# design.net
KiCad netlist of a schematic drawn in Altium Designer
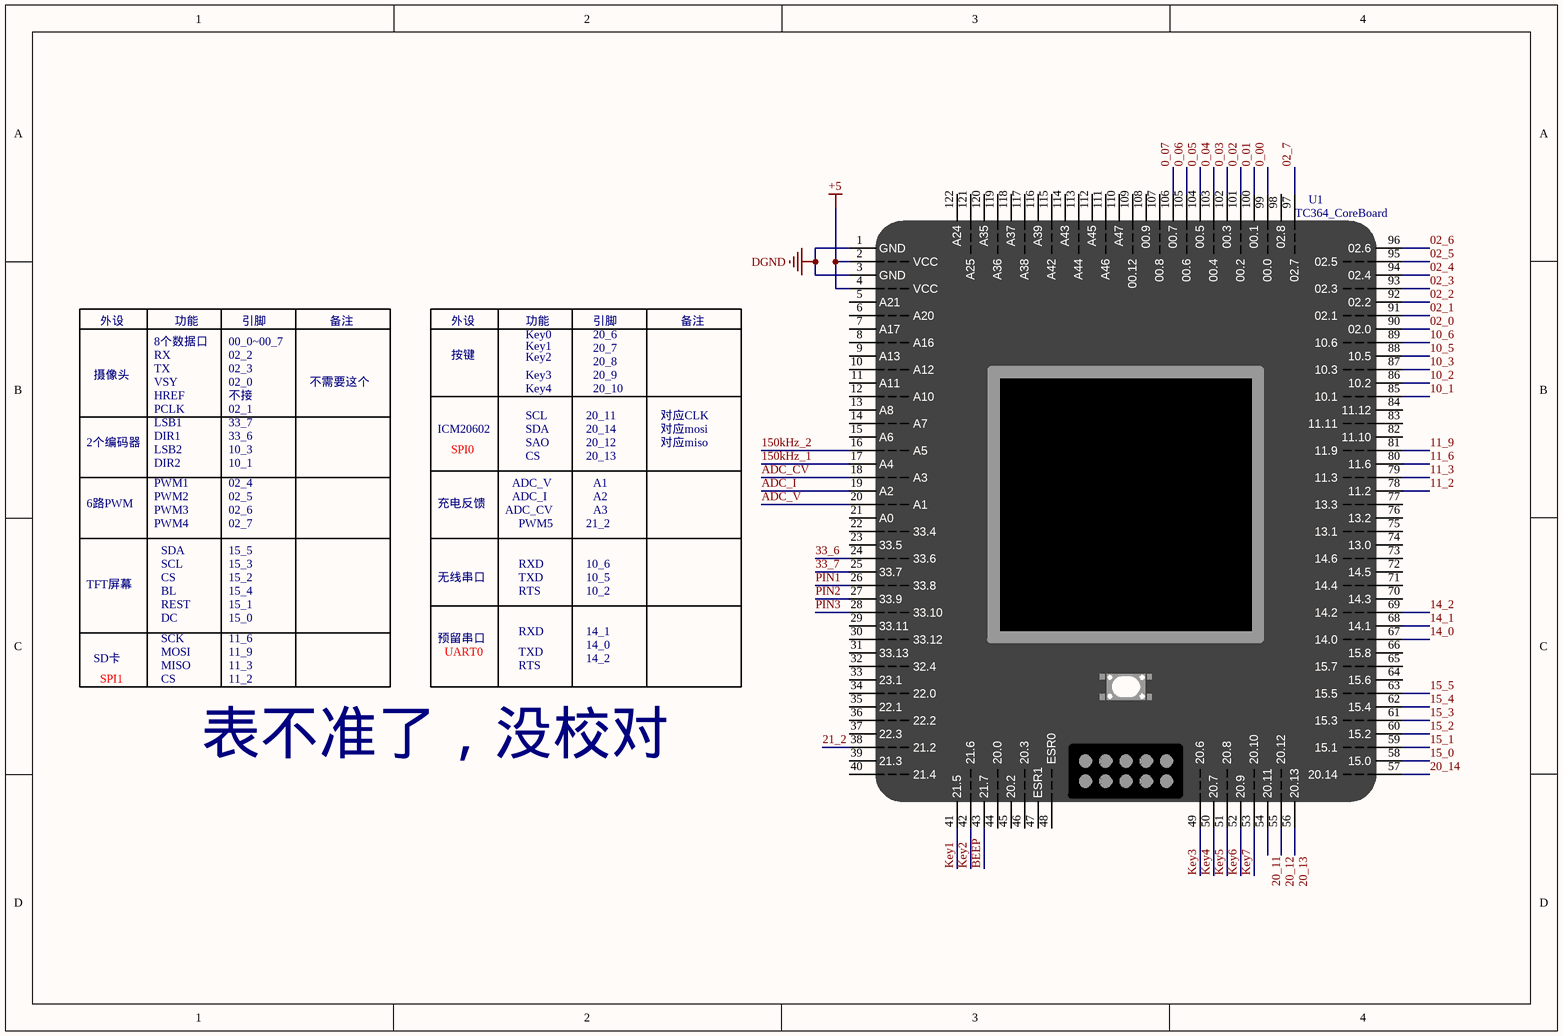
[diagram p0: 主控.SchDoc]

(export (version "E")
  (design (tool "Eeschema 10.0.6"))
  (components
    (comp (ref "U1")
      (value "TC364_CoreBoard")
      (footprint "TC364_CoreBoard")
      (description "逐飞科技TC364核心板")
      (libsource (lib "TC364") (part "TC364_CoreBoard"))
    )
  )
  (nets
    (net (code "1") (name "+5") (class "Default")
      (node (ref "U1") (pin "2") (pinfunction "VCC_2") (pintype "passive"))
      (node (ref "U1") (pin "4") (pinfunction "VCC_4") (pintype "passive"))
    )
    (net (code "2") (name "/0_00") (class "Default")
      (node (ref "U1") (pin "99") (pinfunction "00.0_99") (pintype "passive"))
    )
    (net (code "3") (name "/0_01") (class "Default")
      (node (ref "U1") (pin "100") (pinfunction "00.1_100") (pintype "passive"))
    )
    (net (code "4") (name "/0_02") (class "Default")
      (node (ref "U1") (pin "101") (pinfunction "00.2_101") (pintype "passive"))
    )
    (net (code "5") (name "/0_03") (class "Default")
      (node (ref "U1") (pin "102") (pinfunction "00.3_102") (pintype "passive"))
    )
    (net (code "6") (name "/0_04") (class "Default")
      (node (ref "U1") (pin "103") (pinfunction "00.4_103") (pintype "passive"))
    )
    (net (code "7") (name "/0_05") (class "Default")
      (node (ref "U1") (pin "104") (pinfunction "00.5_104") (pintype "passive"))
    )
    (net (code "8") (name "/0_06") (class "Default")
      (node (ref "U1") (pin "105") (pinfunction "00.6_105") (pintype "passive"))
    )
    (net (code "9") (name "/0_07") (class "Default")
      (node (ref "U1") (pin "106") (pinfunction "00.7_106") (pintype "passive"))
    )
    (net (code "10") (name "/02_0") (class "Default")
      (node (ref "U1") (pin "90") (pinfunction "02.0_90") (pintype "passive"))
    )
    (net (code "11") (name "/02_1") (class "Default")
      (node (ref "U1") (pin "91") (pinfunction "02.1_91") (pintype "passive"))
    )
    (net (code "12") (name "/02_2") (class "Default")
      (node (ref "U1") (pin "92") (pinfunction "02.2_92") (pintype "passive"))
    )
    (net (code "13") (name "/02_3") (class "Default")
      (node (ref "U1") (pin "93") (pinfunction "02.3_93") (pintype "passive"))
    )
    (net (code "14") (name "/02_4") (class "Default")
      (node (ref "U1") (pin "94") (pinfunction "02.4_94") (pintype "passive"))
    )
    (net (code "15") (name "/02_5") (class "Default")
      (node (ref "U1") (pin "95") (pinfunction "02.5_95") (pintype "passive"))
    )
    (net (code "16") (name "/02_6") (class "Default")
      (node (ref "U1") (pin "96") (pinfunction "02.6_96") (pintype "passive"))
    )
    (net (code "17") (name "/02_7") (class "Default")
      (node (ref "U1") (pin "97") (pinfunction "02.7_97") (pintype "passive"))
    )
    (net (code "18") (name "/10_1") (class "Default")
      (node (ref "U1") (pin "85") (pinfunction "10.1_85") (pintype "passive"))
    )
    (net (code "19") (name "/10_2") (class "Default")
      (node (ref "U1") (pin "86") (pinfunction "10.2_86") (pintype "passive"))
    )
    (net (code "20") (name "/10_3") (class "Default")
      (node (ref "U1") (pin "87") (pinfunction "10.3_87") (pintype "passive"))
    )
    (net (code "21") (name "/10_5") (class "Default")
      (node (ref "U1") (pin "88") (pinfunction "10.5_88") (pintype "passive"))
    )
    (net (code "22") (name "/10_6") (class "Default")
      (node (ref "U1") (pin "89") (pinfunction "10.6_89") (pintype "passive"))
    )
    (net (code "23") (name "/11_2") (class "Default")
      (node (ref "U1") (pin "78") (pinfunction "11.2_78") (pintype "passive"))
    )
    (net (code "24") (name "/11_3") (class "Default")
      (node (ref "U1") (pin "79") (pinfunction "11.3_79") (pintype "passive"))
    )
    (net (code "25") (name "/11_6") (class "Default")
      (node (ref "U1") (pin "80") (pinfunction "11.6_80") (pintype "passive"))
    )
    (net (code "26") (name "/11_9") (class "Default")
      (node (ref "U1") (pin "81") (pinfunction "11.9_81") (pintype "passive"))
    )
    (net (code "27") (name "/14_0") (class "Default")
      (node (ref "U1") (pin "67") (pinfunction "14.0_67") (pintype "passive"))
    )
    (net (code "28") (name "/14_1") (class "Default")
      (node (ref "U1") (pin "68") (pinfunction "14.1_68") (pintype "passive"))
    )
    (net (code "29") (name "/14_2") (class "Default")
      (node (ref "U1") (pin "69") (pinfunction "14.2_69") (pintype "passive"))
    )
    (net (code "30") (name "/15_0") (class "Default")
      (node (ref "U1") (pin "58") (pinfunction "15.0_58") (pintype "passive"))
    )
    (net (code "31") (name "/15_1") (class "Default")
      (node (ref "U1") (pin "59") (pinfunction "15.1_59") (pintype "passive"))
    )
    (net (code "32") (name "/15_2") (class "Default")
      (node (ref "U1") (pin "60") (pinfunction "15.2_60") (pintype "passive"))
    )
    (net (code "33") (name "/15_3") (class "Default")
      (node (ref "U1") (pin "61") (pinfunction "15.3_61") (pintype "passive"))
    )
    (net (code "34") (name "/15_4") (class "Default")
      (node (ref "U1") (pin "62") (pinfunction "15.4_62") (pintype "passive"))
    )
    (net (code "35") (name "/15_5") (class "Default")
      (node (ref "U1") (pin "63") (pinfunction "15.5_63") (pintype "passive"))
    )
    (net (code "36") (name "/20_11") (class "Default")
      (node (ref "U1") (pin "54") (pinfunction "20.11_54") (pintype "passive"))
    )
    (net (code "37") (name "/20_12") (class "Default")
      (node (ref "U1") (pin "55") (pinfunction "20.12_55") (pintype "passive"))
    )
    (net (code "38") (name "/20_13") (class "Default")
      (node (ref "U1") (pin "56") (pinfunction "20.13_56") (pintype "passive"))
    )
    (net (code "39") (name "/20_14") (class "Default")
      (node (ref "U1") (pin "57") (pinfunction "20.14_57") (pintype "passive"))
    )
    (net (code "40") (name "/21_2") (class "Default")
      (node (ref "U1") (pin "38") (pinfunction "21.2_38") (pintype "passive"))
    )
    (net (code "41") (name "/33_6") (class "Default")
      (node (ref "U1") (pin "24") (pinfunction "33.6_24") (pintype "passive"))
    )
    (net (code "42") (name "/33_7") (class "Default")
      (node (ref "U1") (pin "25") (pinfunction "33.7_25") (pintype "passive"))
    )
    (net (code "43") (name "/150kHz_1") (class "Default")
      (node (ref "U1") (pin "17") (pinfunction "A4_17") (pintype "passive"))
    )
    (net (code "44") (name "/150kHz_2") (class "Default")
      (node (ref "U1") (pin "16") (pinfunction "A5_16") (pintype "passive"))
    )
    (net (code "46") (name "/ADC_CV") (class "Default")
      (node (ref "U1") (pin "18") (pinfunction "A3_18") (pintype "passive"))
    )
    (net (code "47") (name "/ADC_I") (class "Default")
      (node (ref "U1") (pin "19") (pinfunction "A2_19") (pintype "passive"))
    )
    (net (code "48") (name "/ADC_V") (class "Default")
      (node (ref "U1") (pin "20") (pinfunction "A1_20") (pintype "passive"))
    )
    (net (code "49") (name "/BEEP") (class "Default")
      (node (ref "U1") (pin "43") (pinfunction "21.7_43") (pintype "passive"))
    )
    (net (code "50") (name "/Key1") (class "Default")
      (node (ref "U1") (pin "41") (pinfunction "21.5_41") (pintype "passive"))
    )
    (net (code "51") (name "/Key2") (class "Default")
      (node (ref "U1") (pin "42") (pinfunction "21.6_42") (pintype "passive"))
    )
    (net (code "52") (name "/Key3") (class "Default")
      (node (ref "U1") (pin "49") (pinfunction "20.6_49") (pintype "passive"))
    )
    (net (code "53") (name "/Key4") (class "Default")
      (node (ref "U1") (pin "50") (pinfunction "20.7_50") (pintype "passive"))
    )
    (net (code "54") (name "/Key5") (class "Default")
      (node (ref "U1") (pin "51") (pinfunction "20.8_51") (pintype "passive"))
    )
    (net (code "55") (name "/Key6") (class "Default")
      (node (ref "U1") (pin "52") (pinfunction "20.9_52") (pintype "passive"))
    )
    (net (code "56") (name "/Key7") (class "Default")
      (node (ref "U1") (pin "53") (pinfunction "20.10_53") (pintype "passive"))
    )
    (net (code "57") (name "/PIN1") (class "Default")
      (node (ref "U1") (pin "26") (pinfunction "33.8_26") (pintype "passive"))
    )
    (net (code "58") (name "/PIN2") (class "Default")
      (node (ref "U1") (pin "27") (pinfunction "33.9_27") (pintype "passive"))
    )
    (net (code "59") (name "/PIN3") (class "Default")
      (node (ref "U1") (pin "28") (pinfunction "33.10_28") (pintype "passive"))
    )
    (net (code "60") (name "DGND") (class "Default")
      (node (ref "U1") (pin "1") (pinfunction "GND_1") (pintype "passive"))
      (node (ref "U1") (pin "3") (pinfunction "GND_3") (pintype "passive"))
    )
    (net (code "61") (name "unconnected-(U1-00.8-Pad107)") (class "Default")
      (node (ref "U1") (pin "107") (pinfunction "00.8_107") (pintype "passive"))
    )
    (net (code "62") (name "unconnected-(U1-00.9-Pad108)") (class "Default")
      (node (ref "U1") (pin "108") (pinfunction "00.9_108") (pintype "passive"))
    )
    (net (code "63") (name "unconnected-(U1-00.12-Pad109)") (class "Default")
      (node (ref "U1") (pin "109") (pinfunction "00.12_109") (pintype "passive"))
    )
    (net (code "64") (name "unconnected-(U1-02.8-Pad98)") (class "Default")
      (node (ref "U1") (pin "98") (pinfunction "02.8_98") (pintype "passive"))
    )
    (net (code "65") (name "unconnected-(U1-11.10-Pad82)") (class "Default")
      (node (ref "U1") (pin "82") (pinfunction "11.10_82") (pintype "passive"))
    )
    (net (code "66") (name "unconnected-(U1-11.11-Pad83)") (class "Default")
      (node (ref "U1") (pin "83") (pinfunction "11.11_83") (pintype "passive"))
    )
    (net (code "67") (name "unconnected-(U1-11.12-Pad84)") (class "Default")
      (node (ref "U1") (pin "84") (pinfunction "11.12_84") (pintype "passive"))
    )
    (net (code "68") (name "unconnected-(U1-13.0-Pad74)") (class "Default")
      (node (ref "U1") (pin "74") (pinfunction "13.0_74") (pintype "passive"))
    )
    (net (code "69") (name "unconnected-(U1-13.1-Pad75)") (class "Default")
      (node (ref "U1") (pin "75") (pinfunction "13.1_75") (pintype "passive"))
    )
    (net (code "70") (name "unconnected-(U1-13.2-Pad76)") (class "Default")
      (node (ref "U1") (pin "76") (pinfunction "13.2_76") (pintype "passive"))
    )
    (net (code "71") (name "unconnected-(U1-13.3-Pad77)") (class "Default")
      (node (ref "U1") (pin "77") (pinfunction "13.3_77") (pintype "passive"))
    )
    (net (code "72") (name "unconnected-(U1-14.3-Pad70)") (class "Default")
      (node (ref "U1") (pin "70") (pinfunction "14.3_70") (pintype "passive"))
    )
    (net (code "73") (name "unconnected-(U1-14.4-Pad71)") (class "Default")
      (node (ref "U1") (pin "71") (pinfunction "14.4_71") (pintype "passive"))
    )
    (net (code "74") (name "unconnected-(U1-14.5-Pad72)") (class "Default")
      (node (ref "U1") (pin "72") (pinfunction "14.5_72") (pintype "passive"))
    )
    (net (code "75") (name "unconnected-(U1-14.6-Pad73)") (class "Default")
      (node (ref "U1") (pin "73") (pinfunction "14.6_73") (pintype "passive"))
    )
    (net (code "76") (name "unconnected-(U1-15.6-Pad64)") (class "Default")
      (node (ref "U1") (pin "64") (pinfunction "15.6_64") (pintype "passive"))
    )
    (net (code "77") (name "unconnected-(U1-15.7-Pad65)") (class "Default")
      (node (ref "U1") (pin "65") (pinfunction "15.7_65") (pintype "passive"))
    )
    (net (code "78") (name "unconnected-(U1-15.8-Pad66)") (class "Default")
      (node (ref "U1") (pin "66") (pinfunction "15.8_66") (pintype "passive"))
    )
    (net (code "79") (name "unconnected-(U1-20.0-Pad44)") (class "Default")
      (node (ref "U1") (pin "44") (pinfunction "20.0_44") (pintype "passive"))
    )
    (net (code "80") (name "unconnected-(U1-20.2-Pad45)") (class "Default")
      (node (ref "U1") (pin "45") (pinfunction "20.2_45") (pintype "passive"))
    )
    (net (code "81") (name "unconnected-(U1-20.3-Pad46)") (class "Default")
      (node (ref "U1") (pin "46") (pinfunction "20.3_46") (pintype "passive"))
    )
    (net (code "82") (name "unconnected-(U1-21.3-Pad39)") (class "Default")
      (node (ref "U1") (pin "39") (pinfunction "21.3_39") (pintype "passive"))
    )
    (net (code "83") (name "unconnected-(U1-21.4-Pad40)") (class "Default")
      (node (ref "U1") (pin "40") (pinfunction "21.4_40") (pintype "passive"))
    )
    (net (code "84") (name "unconnected-(U1-22.0-Pad34)") (class "Default")
      (node (ref "U1") (pin "34") (pinfunction "22.0_34") (pintype "passive"))
    )
    (net (code "85") (name "unconnected-(U1-22.1-Pad35)") (class "Default")
      (node (ref "U1") (pin "35") (pinfunction "22.1_35") (pintype "passive"))
    )
    (net (code "86") (name "unconnected-(U1-22.2-Pad36)") (class "Default")
      (node (ref "U1") (pin "36") (pinfunction "22.2_36") (pintype "passive"))
    )
    (net (code "87") (name "unconnected-(U1-22.3-Pad37)") (class "Default")
      (node (ref "U1") (pin "37") (pinfunction "22.3_37") (pintype "passive"))
    )
    (net (code "88") (name "unconnected-(U1-23.1-Pad33)") (class "Default")
      (node (ref "U1") (pin "33") (pinfunction "23.1_33") (pintype "passive"))
    )
    (net (code "89") (name "unconnected-(U1-32.4-Pad32)") (class "Default")
      (node (ref "U1") (pin "32") (pinfunction "32.4_32") (pintype "passive"))
    )
    (net (code "90") (name "unconnected-(U1-33.4-Pad22)") (class "Default")
      (node (ref "U1") (pin "22") (pinfunction "33.4_22") (pintype "passive"))
    )
    (net (code "91") (name "unconnected-(U1-33.5-Pad23)") (class "Default")
      (node (ref "U1") (pin "23") (pinfunction "33.5_23") (pintype "passive"))
    )
    (net (code "92") (name "unconnected-(U1-33.11-Pad29)") (class "Default")
      (node (ref "U1") (pin "29") (pinfunction "33.11_29") (pintype "passive"))
    )
    (net (code "93") (name "unconnected-(U1-33.12-Pad30)") (class "Default")
      (node (ref "U1") (pin "30") (pinfunction "33.12_30") (pintype "passive"))
    )
    (net (code "94") (name "unconnected-(U1-33.13-Pad31)") (class "Default")
      (node (ref "U1") (pin "31") (pinfunction "33.13_31") (pintype "passive"))
    )
    (net (code "95") (name "unconnected-(U1-A0-Pad21)") (class "Default")
      (node (ref "U1") (pin "21") (pinfunction "A0_21") (pintype "passive"))
    )
    (net (code "96") (name "unconnected-(U1-A6-Pad15)") (class "Default")
      (node (ref "U1") (pin "15") (pinfunction "A6_15") (pintype "passive"))
    )
    (net (code "97") (name "unconnected-(U1-A7-Pad14)") (class "Default")
      (node (ref "U1") (pin "14") (pinfunction "A7_14") (pintype "passive"))
    )
    (net (code "98") (name "unconnected-(U1-A8-Pad13)") (class "Default")
      (node (ref "U1") (pin "13") (pinfunction "A8_13") (pintype "passive"))
    )
    (net (code "99") (name "unconnected-(U1-A10-Pad12)") (class "Default")
      (node (ref "U1") (pin "12") (pinfunction "A10_12") (pintype "passive"))
    )
    (net (code "100") (name "unconnected-(U1-A11-Pad11)") (class "Default")
      (node (ref "U1") (pin "11") (pinfunction "A11_11") (pintype "passive"))
    )
    (net (code "101") (name "unconnected-(U1-A12-Pad10)") (class "Default")
      (node (ref "U1") (pin "10") (pinfunction "A12_10") (pintype "passive"))
    )
    (net (code "102") (name "unconnected-(U1-A13-Pad9)") (class "Default")
      (node (ref "U1") (pin "9") (pinfunction "A13_9") (pintype "passive"))
    )
    (net (code "103") (name "unconnected-(U1-A16-Pad8)") (class "Default")
      (node (ref "U1") (pin "8") (pinfunction "A16_8") (pintype "passive"))
    )
    (net (code "104") (name "unconnected-(U1-A17-Pad7)") (class "Default")
      (node (ref "U1") (pin "7") (pinfunction "A17_7") (pintype "passive"))
    )
    (net (code "105") (name "unconnected-(U1-A20-Pad6)") (class "Default")
      (node (ref "U1") (pin "6") (pinfunction "A20_6") (pintype "passive"))
    )
    (net (code "106") (name "unconnected-(U1-A21-Pad5)") (class "Default")
      (node (ref "U1") (pin "5") (pinfunction "A21_5") (pintype "passive"))
    )
    (net (code "107") (name "unconnected-(U1-A24-Pad122)") (class "Default")
      (node (ref "U1") (pin "122") (pinfunction "A24_122") (pintype "passive"))
    )
    (net (code "108") (name "unconnected-(U1-A25-Pad121)") (class "Default")
      (node (ref "U1") (pin "121") (pinfunction "A25_121") (pintype "passive"))
    )
    (net (code "109") (name "unconnected-(U1-A35-Pad120)") (class "Default")
      (node (ref "U1") (pin "120") (pinfunction "A35_120") (pintype "passive"))
    )
    (net (code "110") (name "unconnected-(U1-A36-Pad119)") (class "Default")
      (node (ref "U1") (pin "119") (pinfunction "A36_119") (pintype "passive"))
    )
    (net (code "111") (name "unconnected-(U1-A37-Pad118)") (class "Default")
      (node (ref "U1") (pin "118") (pinfunction "A37_118") (pintype "passive"))
    )
    (net (code "112") (name "unconnected-(U1-A38-Pad117)") (class "Default")
      (node (ref "U1") (pin "117") (pinfunction "A38_117") (pintype "passive"))
    )
    (net (code "113") (name "unconnected-(U1-A39-Pad116)") (class "Default")
      (node (ref "U1") (pin "116") (pinfunction "A39_116") (pintype "passive"))
    )
    (net (code "114") (name "unconnected-(U1-A42-Pad115)") (class "Default")
      (node (ref "U1") (pin "115") (pinfunction "A42_115") (pintype "passive"))
    )
    (net (code "115") (name "unconnected-(U1-A43-Pad114)") (class "Default")
      (node (ref "U1") (pin "114") (pinfunction "A43_114") (pintype "passive"))
    )
    (net (code "116") (name "unconnected-(U1-A44-Pad113)") (class "Default")
      (node (ref "U1") (pin "113") (pinfunction "A44_113") (pintype "passive"))
    )
    (net (code "117") (name "unconnected-(U1-A45-Pad112)") (class "Default")
      (node (ref "U1") (pin "112") (pinfunction "A45_112") (pintype "passive"))
    )
    (net (code "118") (name "unconnected-(U1-A46-Pad111)") (class "Default")
      (node (ref "U1") (pin "111") (pinfunction "A46_111") (pintype "passive"))
    )
    (net (code "119") (name "unconnected-(U1-A47-Pad110)") (class "Default")
      (node (ref "U1") (pin "110") (pinfunction "A47_110") (pintype "passive"))
    )
    (net (code "120") (name "unconnected-(U1-ESR0-Pad48)") (class "Default")
      (node (ref "U1") (pin "48") (pinfunction "ESR0_48") (pintype "passive"))
    )
    (net (code "121") (name "unconnected-(U1-ESR1-Pad47)") (class "Default")
      (node (ref "U1") (pin "47") (pinfunction "ESR1_47") (pintype "passive"))
    )
  )
)
